# ECGAquisitionBoard.net
KiCad netlist of a schematic drawn in Altium Designer
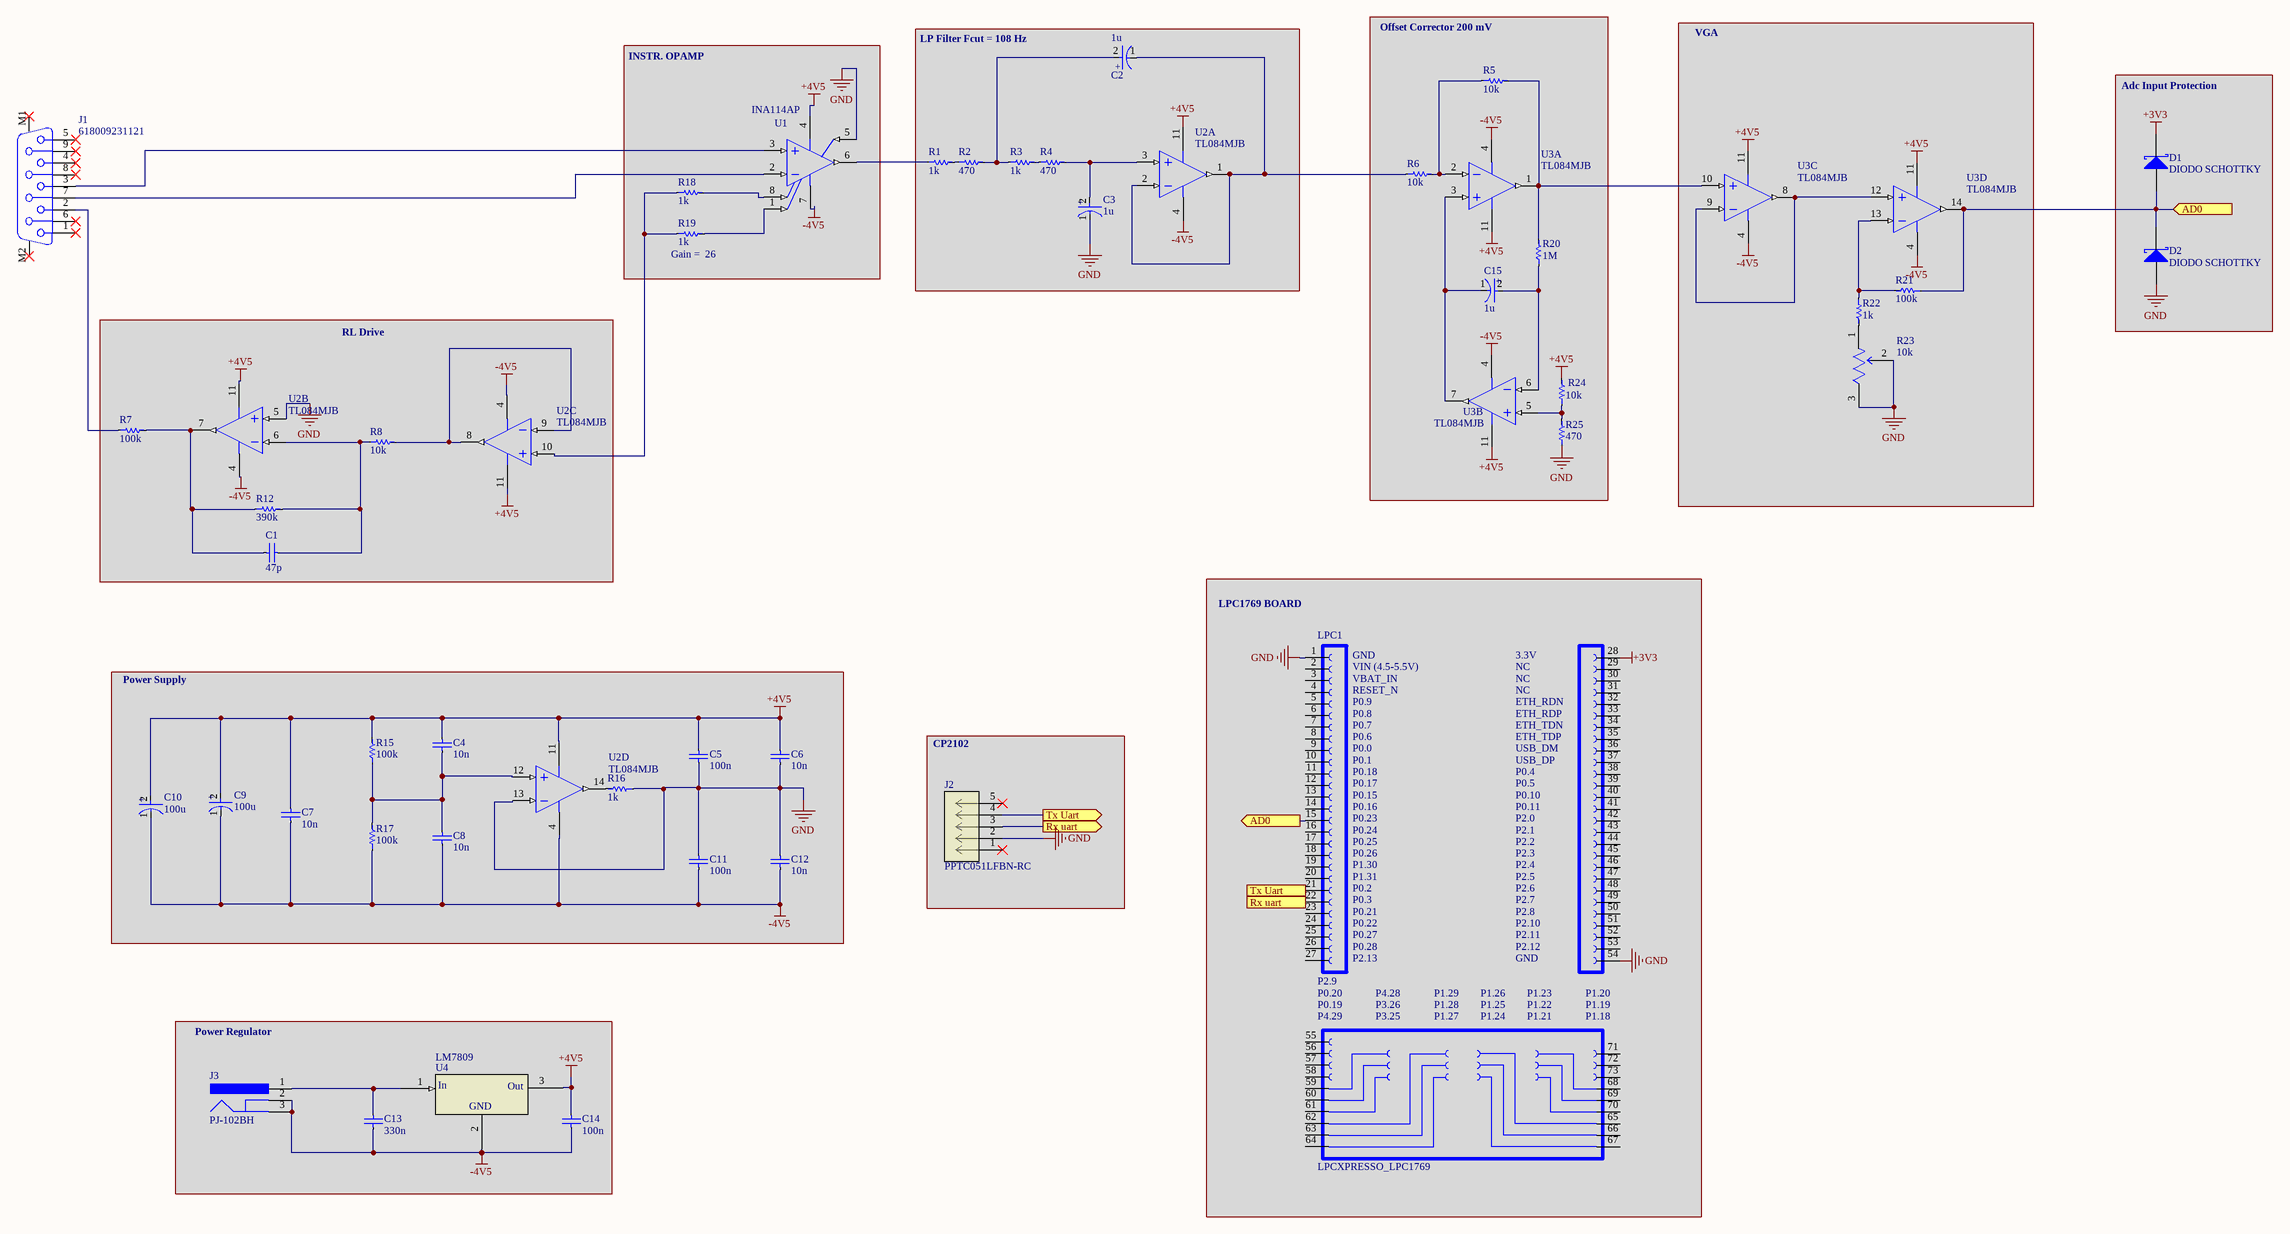
[diagram p0: ECGAquisitionBoard.SchDoc]

(export (version "E")
  (design (tool "Eeschema 10.0.6"))
  (components
    (comp (ref "C1")
      (value "47p")
      (footprint "CAP SMD 1206")
      (description "CAP 330nF 50V ±10% 1206 (3216 Metric) Thickness 1.9mm SMD")
      (fields (field (name "TOLERANCE") "Â±10%"))
      (libsource (lib "ECGAquisitionBoard") (part "CAP SMD 1206"))
    )
    (comp (ref "C2")
      (value "1u")
      (footprint "FP-RAD-TH-D_5_0_5-L_11_1-MFG")
      (description "Aluminum Electrolytic Capacitors (Radial Lead Type) AEC-Q200 Qualified 10uF ±20% 50V")
      (fields (field (name "TOLERANCE") "20%"))
      (libsource (lib "Altium Content Vault") (part "a00bbbee19879c290e62620ae7e47b1"))
    )
    (comp (ref "C3")
      (value "1u")
      (footprint "FP-RAD-TH-D_5_0_5-L_11_1-MFG")
      (description "Aluminum Electrolytic Capacitors (Radial Lead Type) AEC-Q200 Qualified 10uF ±20% 50V")
      (fields (field (name "TOLERANCE") "20%"))
      (libsource (lib "Altium Content Vault") (part "a00bbbee19879c290e62620ae7e47b1"))
    )
    (comp (ref "C4")
      (value "10n")
      (footprint "CAP SMD 1206")
      (description "CAP 330nF 50V ±10% 1206 (3216 Metric) Thickness 1.9mm SMD")
      (fields (field (name "TOLERANCE") "Â±10%"))
      (libsource (lib "ECGAquisitionBoard") (part "CAP SMD 1206"))
    )
    (comp (ref "C5")
      (value "100n")
      (footprint "CAP SMD 1206")
      (description "CAP 330nF 50V ±10% 1206 (3216 Metric) Thickness 1.9mm SMD")
      (fields (field (name "TOLERANCE") "Â±10%"))
      (libsource (lib "ECGAquisitionBoard") (part "CAP SMD 1206"))
    )
    (comp (ref "C6")
      (value "10n")
      (footprint "CAP SMD 1206")
      (description "CAP 330nF 50V ±10% 1206 (3216 Metric) Thickness 1.9mm SMD")
      (fields (field (name "TOLERANCE") "Â±10%"))
      (libsource (lib "ECGAquisitionBoard") (part "CAP SMD 1206"))
    )
    (comp (ref "C7")
      (value "10n")
      (footprint "CAP SMD 1206")
      (description "CAP 330nF 50V ±10% 1206 (3216 Metric) Thickness 1.9mm SMD")
      (fields (field (name "TOLERANCE") "Â±10%"))
      (libsource (lib "ECGAquisitionBoard") (part "CAP SMD 1206"))
    )
    (comp (ref "C8")
      (value "10n")
      (footprint "CAP SMD 1206")
      (description "CAP 330nF 50V ±10% 1206 (3216 Metric) Thickness 1.9mm SMD")
      (fields (field (name "TOLERANCE") "Â±10%"))
      (libsource (lib "ECGAquisitionBoard") (part "CAP SMD 1206"))
    )
    (comp (ref "C9")
      (value "100u")
      (footprint "FP-RAD-TH-D_5_0_5-L_11_1-MFG")
      (description "Aluminum Electrolytic Capacitors (Radial Lead Type) AEC-Q200 Qualified 10uF ±20% 50V")
      (fields (field (name "TOLERANCE") "20%"))
      (libsource (lib "Altium Content Vault") (part "a00bbbee19879c290e62620ae7e47b1"))
    )
    (comp (ref "C10")
      (value "100u")
      (footprint "FP-RAD-TH-D_5_0_5-L_11_1-MFG")
      (description "Aluminum Electrolytic Capacitors (Radial Lead Type) AEC-Q200 Qualified 10uF ±20% 50V")
      (fields (field (name "TOLERANCE") "20%"))
      (libsource (lib "Altium Content Vault") (part "a00bbbee19879c290e62620ae7e47b1"))
    )
    (comp (ref "C11")
      (value "100n")
      (footprint "CAP SMD 1206")
      (description "CAP 330nF 50V ±10% 1206 (3216 Metric) Thickness 1.9mm SMD")
      (fields (field (name "TOLERANCE") "Â±10%"))
      (libsource (lib "ECGAquisitionBoard") (part "CAP SMD 1206"))
    )
    (comp (ref "C12")
      (value "10n")
      (footprint "CAP SMD 1206")
      (description "CAP 330nF 50V ±10% 1206 (3216 Metric) Thickness 1.9mm SMD")
      (fields (field (name "TOLERANCE") "Â±10%"))
      (libsource (lib "ECGAquisitionBoard") (part "CAP SMD 1206"))
    )
    (comp (ref "C13")
      (value "330n")
      (footprint "CAP SMD 1206")
      (description "CAP 330nF 50V ±10% 1206 (3216 Metric) Thickness 1.9mm SMD")
      (fields (field (name "TOLERANCE") "Â±10%"))
      (libsource (lib "ECGAquisitionBoard") (part "CAP SMD 1206"))
    )
    (comp (ref "C14")
      (value "100n")
      (footprint "CAP SMD 1206")
      (description "CAP 330nF 50V ±10% 1206 (3216 Metric) Thickness 1.9mm SMD")
      (fields (field (name "TOLERANCE") "Â±10%"))
      (libsource (lib "ECGAquisitionBoard") (part "CAP SMD 1206"))
    )
    (comp (ref "C15")
      (value "1u")
      (footprint "FP-RAD-TH-D_5_0_5-L_11_1-MFG")
      (description "Aluminum Electrolytic Capacitors (Radial Lead Type) AEC-Q200 Qualified 10uF ±20% 50V")
      (fields (field (name "TOLERANCE") "20%"))
      (libsource (lib "Altium Content Vault") (part "a00bbbee19879c290e62620ae7e47b1"))
    )
    (comp (ref "D1")
      (value "DIODO SCHOTTKY")
      (footprint "DO-41")
      (description "Diodo Schottky")
      (libsource (lib "ECGAquisitionBoard") (part "DIODO SCHOTTKY"))
    )
    (comp (ref "D2")
      (value "DIODO SCHOTTKY")
      (footprint "DO-41")
      (description "Diodo Schottky")
      (libsource (lib "ECGAquisitionBoard") (part "DIODO SCHOTTKY"))
    )
    (comp (ref "J1")
      (value "618009231121")
      (footprint "618009231121")
      (libsource (lib "Altium Content Vault") (part "D-Sub_Female_09p"))
    )
    (comp (ref "J2")
      (value "PPTC051LFBN-RC")
      (footprint "HEADER 5 F 90DEG")
      (description "Description")
      (fields (field (name "COPYRIGHT") "Copyright (C) 2025 Ultra Librarian. All rights reserved."))
      (libsource (lib "ECGAquisitionBoard") (part "HEADER 5 F 90DEG"))
    )
    (comp (ref "J3")
      (value "PJ-102BH")
      (footprint "CUI-PJ-102BH_V")
      (fields (field (name "MANUFACTURER") "CUIInc."))
      (libsource (lib "Altium Content Vault") (part "JACK-2CD3-RN"))
    )
    (comp (ref "LPC1")
      (value "LPCXPRESSO_LPC1769")
      (footprint "LPCXPRESSO_LPC1769")
      (fields (field (name "MF") "Embedded Artists") (field (name "MP") "LPCXPRESSO LPC1769"))
      (libsource (lib "ECGAquisitionBoard") (part "LPCXPRESSO_LPC1769"))
    )
    (comp (ref "R1")
      (value "1k")
      (footprint "RES SMD 1206")
      (description "Resistencia")
      (fields (field (name "PUBLISHER") "Altium Limited"))
      (libsource (lib "ECGAquisitionBoard") (part "RES SMD 1206"))
    )
    (comp (ref "R2")
      (value "470")
      (footprint "RES SMD 1206")
      (description "Resistencia")
      (fields (field (name "PUBLISHER") "Altium Limited"))
      (libsource (lib "ECGAquisitionBoard") (part "RES SMD 1206"))
    )
    (comp (ref "R3")
      (value "1k")
      (footprint "RES SMD 1206")
      (description "Resistencia")
      (fields (field (name "PUBLISHER") "Altium Limited"))
      (libsource (lib "ECGAquisitionBoard") (part "RES SMD 1206"))
    )
    (comp (ref "R4")
      (value "470")
      (footprint "RES SMD 1206")
      (description "Resistencia")
      (fields (field (name "PUBLISHER") "Altium Limited"))
      (libsource (lib "ECGAquisitionBoard") (part "RES SMD 1206"))
    )
    (comp (ref "R5")
      (value "10k")
      (footprint "RES SMD 1206")
      (description "Resistencia")
      (fields (field (name "PUBLISHER") "Altium Limited"))
      (libsource (lib "ECGAquisitionBoard") (part "RES SMD 1206"))
    )
    (comp (ref "R6")
      (value "10k")
      (footprint "RES SMD 1206")
      (description "Resistencia")
      (fields (field (name "PUBLISHER") "Altium Limited"))
      (libsource (lib "ECGAquisitionBoard") (part "RES SMD 1206"))
    )
    (comp (ref "R7")
      (value "100k")
      (footprint "RES SMD 1206")
      (description "Resistencia")
      (fields (field (name "PUBLISHER") "Altium Limited"))
      (libsource (lib "ECGAquisitionBoard") (part "RES SMD 1206"))
    )
    (comp (ref "R8")
      (value "10k")
      (footprint "RES SMD 1206")
      (description "Resistencia")
      (fields (field (name "PUBLISHER") "Altium Limited"))
      (libsource (lib "ECGAquisitionBoard") (part "RES SMD 1206"))
    )
    (comp (ref "R12")
      (value "390k")
      (footprint "RES SMD 1206")
      (description "Resistencia")
      (fields (field (name "PUBLISHER") "Altium Limited"))
      (libsource (lib "ECGAquisitionBoard") (part "RES SMD 1206"))
    )
    (comp (ref "R15")
      (value "100k")
      (footprint "RES SMD 1206")
      (description "Resistencia")
      (fields (field (name "PUBLISHER") "Altium Limited"))
      (libsource (lib "ECGAquisitionBoard") (part "RES SMD 1206"))
    )
    (comp (ref "R16")
      (value "1k")
      (footprint "RES SMD 1206")
      (description "Resistencia")
      (fields (field (name "PUBLISHER") "Altium Limited"))
      (libsource (lib "ECGAquisitionBoard") (part "RES SMD 1206"))
    )
    (comp (ref "R17")
      (value "100k")
      (footprint "RES SMD 1206")
      (description "Resistencia")
      (fields (field (name "PUBLISHER") "Altium Limited"))
      (libsource (lib "ECGAquisitionBoard") (part "RES SMD 1206"))
    )
    (comp (ref "R18")
      (value "1k")
      (footprint "RES SMD 1206")
      (description "Resistencia")
      (fields (field (name "PUBLISHER") "Altium Limited"))
      (libsource (lib "ECGAquisitionBoard") (part "RES SMD 1206"))
    )
    (comp (ref "R19")
      (value "1k")
      (footprint "RES SMD 1206")
      (description "Resistencia")
      (fields (field (name "PUBLISHER") "Altium Limited"))
      (libsource (lib "ECGAquisitionBoard") (part "RES SMD 1206"))
    )
    (comp (ref "R20")
      (value "1M")
      (footprint "RES SMD 1206")
      (description "Resistencia")
      (fields (field (name "PUBLISHER") "Altium Limited"))
      (libsource (lib "ECGAquisitionBoard") (part "RES SMD 1206"))
    )
    (comp (ref "R21")
      (value "100k")
      (footprint "RES SMD 1206")
      (description "Resistencia")
      (fields (field (name "PUBLISHER") "Altium Limited"))
      (libsource (lib "ECGAquisitionBoard") (part "RES SMD 1206"))
    )
    (comp (ref "R22")
      (value "1k")
      (footprint "RES SMD 1206")
      (description "Resistencia")
      (fields (field (name "PUBLISHER") "Altium Limited"))
      (libsource (lib "ECGAquisitionBoard") (part "RES SMD 1206"))
    )
    (comp (ref "R23")
      (value "10k")
      (footprint "FP-3296W-MFG")
      (description "TRIMMER 10K OHM 0.5W PC PIN TOP")
      (fields (field (name "TOLERANCE") "10%"))
      (libsource (lib "Altium Content Vault") (part "194907ebf2981c0cdd5d9631a0af656"))
    )
    (comp (ref "R24")
      (value "10k")
      (footprint "RES SMD 1206")
      (description "Resistencia")
      (fields (field (name "PUBLISHER") "Altium Limited"))
      (libsource (lib "ECGAquisitionBoard") (part "RES SMD 1206"))
    )
    (comp (ref "R25")
      (value "470")
      (footprint "RES SMD 1206")
      (description "Resistencia")
      (fields (field (name "PUBLISHER") "Altium Limited"))
      (libsource (lib "ECGAquisitionBoard") (part "RES SMD 1206"))
    )
    (comp (ref "U1")
      (value "INA114AP")
      (footprint "P0008A")
      (description "Precision Instrumentation Amplifier, -40 to 85 degC, 8-pin DIP (P8), Green (RoHS & no Sb/Br)")
      (fields (field (name "MANUFACTURER") "Texas Instruments"))
      (libsource (lib "Altium Content Vault") (part "TI-INA1XX-8"))
    )
    (comp (ref "U2")
      (value "TL084MJB")
      (footprint "J0014A")
      (description "High Speed JFET-Input Quad Operational Amplifier, -55 to 125 degC, 14-pin DIP (J14)")
      (fields (field (name "MANUFACTURER") "Texas Instruments"))
      (libsource (lib "Altium Content Vault") (part "TI-TLXX4X_MC3403-X14"))
    )
    (comp (ref "U3")
      (value "TL084MJB")
      (footprint "J0014A")
      (description "High Speed JFET-Input Quad Operational Amplifier, -55 to 125 degC, 14-pin DIP (J14)")
      (fields (field (name "MANUFACTURER") "Texas Instruments"))
      (libsource (lib "Altium Content Vault") (part "TI-TLXX4X_MC3403-X14"))
    )
    (comp (ref "U4")
      (value "LM7809")
      (footprint "LM7809")
      (description "No Description Available")
      (fields
        (field (name "MANUFACTURER_PART_NUMBER") "MC7809CTG")
        (field (name "COPYRIGHT") "Copyright (C) 2025 Ultra Librarian. All rights reserved.")
      )
      (libsource (lib "ECGAquisitionBoard") (part "LM7809"))
    )
  )
  (nets
    (net (code "1") (name "+3V3") (class "Default")
      (node (ref "D1") (pin "2") (pinfunction "K_2") (pintype "passive"))
      (node (ref "LPC1") (pin "28") (pinfunction "28_28") (pintype "passive"))
    )
    (net (code "2") (name "+4V5") (class "Default")
      (node (ref "C10") (pin "2") (pinfunction "A_2") (pintype "passive"))
      (node (ref "C14") (pin "2") (pinfunction "2_2") (pintype "passive"))
      (node (ref "C4") (pin "2") (pinfunction "2_2") (pintype "passive"))
      (node (ref "C5") (pin "2") (pinfunction "2_2") (pintype "passive"))
      (node (ref "C6") (pin "2") (pinfunction "2_2") (pintype "passive"))
      (node (ref "C7") (pin "2") (pinfunction "2_2") (pintype "passive"))
      (node (ref "C9") (pin "2") (pinfunction "A_2") (pintype "passive"))
      (node (ref "R15") (pin "2") (pinfunction "2_2") (pintype "passive"))
      (node (ref "R24") (pin "2") (pinfunction "2_2") (pintype "passive"))
      (node (ref "U1") (pin "4") (pinfunction "V-_4") (pintype "power_in"))
      (node (ref "U2") (pin "11") (pinfunction "VCC-_11") (pintype "power_in"))
      (node (ref "U3") (pin "11") (pinfunction "VCC-_11") (pintype "power_in"))
      (node (ref "U4") (pin "3") (pinfunction "OUTPUT_3") (pintype "power_in"))
    )
    (net (code "3") (name "-4V5") (class "Default")
      (node (ref "C10") (pin "1") (pinfunction "C_1") (pintype "passive"))
      (node (ref "C11") (pin "1") (pinfunction "1_1") (pintype "passive"))
      (node (ref "C12") (pin "1") (pinfunction "1_1") (pintype "passive"))
      (node (ref "C13") (pin "1") (pinfunction "1_1") (pintype "passive"))
      (node (ref "C14") (pin "1") (pinfunction "1_1") (pintype "passive"))
      (node (ref "C7") (pin "1") (pinfunction "1_1") (pintype "passive"))
      (node (ref "C8") (pin "1") (pinfunction "1_1") (pintype "passive"))
      (node (ref "C9") (pin "1") (pinfunction "C_1") (pintype "passive"))
      (node (ref "J3") (pin "2") (pinfunction "2_2") (pintype "passive"))
      (node (ref "J3") (pin "3") (pinfunction "3_3") (pintype "passive"))
      (node (ref "R17") (pin "1") (pinfunction "1_1") (pintype "passive"))
      (node (ref "U1") (pin "7") (pinfunction "V+_7") (pintype "power_in"))
      (node (ref "U2") (pin "4") (pinfunction "VCC+_4") (pintype "power_in"))
      (node (ref "U3") (pin "4") (pinfunction "VCC+_4") (pintype "power_in"))
      (node (ref "U4") (pin "2") (pinfunction "GROUND_2") (pintype "power_in"))
    )
    (net (code "4") (name "/AD0") (class "Default")
      (node (ref "D1") (pin "1") (pinfunction "A_1") (pintype "passive"))
      (node (ref "D2") (pin "2") (pinfunction "K_2") (pintype "passive"))
      (node (ref "LPC1") (pin "15") (pinfunction "15_15") (pintype "passive"))
      (node (ref "R21") (pin "1") (pinfunction "1_1") (pintype "passive"))
      (node (ref "U3") (pin "14") (pinfunction "OUT4_14") (pintype "output"))
    )
    (net (code "5") (name "/Rx uart") (class "Default")
      (node (ref "J2") (pin "3") (pinfunction "3_3") (pintype "passive"))
      (node (ref "LPC1") (pin "22") (pinfunction "22_22") (pintype "passive"))
    )
    (net (code "6") (name "/Tx Uart") (class "Default")
      (node (ref "J2") (pin "4") (pinfunction "4_4") (pintype "passive"))
      (node (ref "LPC1") (pin "21") (pinfunction "21_21") (pintype "passive"))
    )
    (net (code "7") (name "GND") (class "Default")
      (node (ref "C11") (pin "2") (pinfunction "2_2") (pintype "passive"))
      (node (ref "C12") (pin "2") (pinfunction "2_2") (pintype "passive"))
      (node (ref "C3") (pin "1") (pinfunction "C_1") (pintype "passive"))
      (node (ref "C5") (pin "1") (pinfunction "1_1") (pintype "passive"))
      (node (ref "C6") (pin "1") (pinfunction "1_1") (pintype "passive"))
      (node (ref "D2") (pin "1") (pinfunction "A_1") (pintype "passive"))
      (node (ref "J2") (pin "2") (pinfunction "2_2") (pintype "passive"))
      (node (ref "LPC1") (pin "1") (pinfunction "1_1") (pintype "passive"))
      (node (ref "LPC1") (pin "54") (pinfunction "54_54") (pintype "passive"))
      (node (ref "R16") (pin "1") (pinfunction "1_1") (pintype "passive"))
      (node (ref "R23") (pin "2") (pinfunction "WIPER_2") (pintype "passive"))
      (node (ref "R23") (pin "3") (pinfunction "CW_3") (pintype "passive"))
      (node (ref "R25") (pin "1") (pinfunction "1_1") (pintype "passive"))
      (node (ref "U1") (pin "5") (pinfunction "REF_5") (pintype "input"))
      (node (ref "U2") (pin "13") (pinfunction "IN4-_13") (pintype "input"))
      (node (ref "U2") (pin "5") (pinfunction "IN2+_5") (pintype "input"))
    )
    (net (code "8") (name "Net-(C2-A)") (class "Default")
      (node (ref "C2") (pin "2") (pinfunction "A_2") (pintype "passive"))
      (node (ref "R2") (pin "2") (pinfunction "2_2") (pintype "passive"))
      (node (ref "R3") (pin "1") (pinfunction "1_1") (pintype "passive"))
    )
    (net (code "9") (name "Net-(C2-C)") (class "Default")
      (node (ref "C2") (pin "1") (pinfunction "C_1") (pintype "passive"))
      (node (ref "R6") (pin "1") (pinfunction "1_1") (pintype "passive"))
      (node (ref "U2") (pin "1") (pinfunction "OUT1_1") (pintype "output"))
      (node (ref "U2") (pin "2") (pinfunction "IN1-_2") (pintype "input"))
    )
    (net (code "10") (name "Net-(C3-A)") (class "Default")
      (node (ref "C3") (pin "2") (pinfunction "A_2") (pintype "passive"))
      (node (ref "R4") (pin "2") (pinfunction "2_2") (pintype "passive"))
      (node (ref "U2") (pin "3") (pinfunction "IN1+_3") (pintype "input"))
    )
    (net (code "11") (name "Net-(C15-A)") (class "Default")
      (node (ref "C15") (pin "2") (pinfunction "A_2") (pintype "passive"))
      (node (ref "R20") (pin "1") (pinfunction "1_1") (pintype "passive"))
      (node (ref "U3") (pin "6") (pinfunction "IN2-_6") (pintype "input"))
    )
    (net (code "12") (name "Net-(C15-C)") (class "Default")
      (node (ref "C15") (pin "1") (pinfunction "C_1") (pintype "passive"))
      (node (ref "U3") (pin "3") (pinfunction "IN1+_3") (pintype "input"))
      (node (ref "U3") (pin "7") (pinfunction "OUT2_7") (pintype "output"))
    )
    (net (code "13") (name "Net-(J1-Pad2)") (class "Default")
      (node (ref "J1") (pin "2") (pinfunction "2_2") (pintype "passive"))
      (node (ref "R7") (pin "1") (pinfunction "1_1") (pintype "passive"))
    )
    (net (code "14") (name "Net-(R1-Pad2)") (class "Default")
      (node (ref "R1") (pin "2") (pinfunction "2_2") (pintype "passive"))
      (node (ref "R2") (pin "1") (pinfunction "1_1") (pintype "passive"))
    )
    (net (code "15") (name "Net-(R3-Pad2)") (class "Default")
      (node (ref "R3") (pin "2") (pinfunction "2_2") (pintype "passive"))
      (node (ref "R4") (pin "1") (pinfunction "1_1") (pintype "passive"))
    )
    (net (code "16") (name "Net-(R18-Pad2)") (class "Default")
      (node (ref "R18") (pin "2") (pinfunction "2_2") (pintype "passive"))
      (node (ref "U1") (pin "8") (pinfunction "RG_8") (pintype "input"))
    )
    (net (code "17") (name "Net-(R19-Pad2)") (class "Default")
      (node (ref "R19") (pin "2") (pinfunction "2_2") (pintype "passive"))
      (node (ref "U1") (pin "1") (pinfunction "RG_1") (pintype "input"))
    )
    (net (code "18") (name "Net-(R23-CCW)") (class "Default")
      (node (ref "R22") (pin "2") (pinfunction "2_2") (pintype "passive"))
      (node (ref "R23") (pin "1") (pinfunction "CCW_1") (pintype "passive"))
    )
    (net (code "19") (name "Net-(U1-VIN+)") (class "Default")
      (node (ref "J1") (pin "3") (pinfunction "3_3") (pintype "passive"))
      (node (ref "U1") (pin "3") (pinfunction "VIN+_3") (pintype "input"))
    )
    (net (code "20") (name "Net-(U1-VIN-)") (class "Default")
      (node (ref "J1") (pin "7") (pinfunction "7_7") (pintype "passive"))
      (node (ref "U1") (pin "2") (pinfunction "VIN-_2") (pintype "input"))
    )
    (net (code "21") (name "Net-(U1-VO)") (class "Default")
      (node (ref "R1") (pin "1") (pinfunction "1_1") (pintype "passive"))
      (node (ref "U1") (pin "6") (pinfunction "VO_6") (pintype "output"))
    )
    (net (code "22") (name "Net-(U2B-IN2-)") (class "Default")
      (node (ref "C1") (pin "2") (pinfunction "2_2") (pintype "passive"))
      (node (ref "R12") (pin "2") (pinfunction "2_2") (pintype "passive"))
      (node (ref "R8") (pin "1") (pinfunction "1_1") (pintype "passive"))
      (node (ref "U2") (pin "6") (pinfunction "IN2-_6") (pintype "input"))
    )
    (net (code "23") (name "Net-(U2B-OUT2)") (class "Default")
      (node (ref "C1") (pin "1") (pinfunction "1_1") (pintype "passive"))
      (node (ref "R12") (pin "1") (pinfunction "1_1") (pintype "passive"))
      (node (ref "R7") (pin "2") (pinfunction "2_2") (pintype "passive"))
      (node (ref "U2") (pin "7") (pinfunction "OUT2_7") (pintype "output"))
    )
    (net (code "24") (name "Net-(U2C-IN3+)") (class "Default")
      (node (ref "R18") (pin "1") (pinfunction "1_1") (pintype "passive"))
      (node (ref "R19") (pin "1") (pinfunction "1_1") (pintype "passive"))
      (node (ref "U2") (pin "10") (pinfunction "IN3+_10") (pintype "input"))
    )
    (net (code "25") (name "Net-(U2C-IN3-)") (class "Default")
      (node (ref "R8") (pin "2") (pinfunction "2_2") (pintype "passive"))
      (node (ref "U2") (pin "8") (pinfunction "OUT3_8") (pintype "output"))
      (node (ref "U2") (pin "9") (pinfunction "IN3-_9") (pintype "input"))
    )
    (net (code "26") (name "Net-(U2D-IN4+)") (class "Default")
      (node (ref "C4") (pin "1") (pinfunction "1_1") (pintype "passive"))
      (node (ref "C8") (pin "2") (pinfunction "2_2") (pintype "passive"))
      (node (ref "R15") (pin "1") (pinfunction "1_1") (pintype "passive"))
      (node (ref "R17") (pin "2") (pinfunction "2_2") (pintype "passive"))
      (node (ref "U2") (pin "12") (pinfunction "IN4+_12") (pintype "input"))
    )
    (net (code "27") (name "Net-(U2D-OUT4)") (class "Default")
      (node (ref "R16") (pin "2") (pinfunction "2_2") (pintype "passive"))
      (node (ref "U2") (pin "14") (pinfunction "OUT4_14") (pintype "output"))
    )
    (net (code "28") (name "Net-(U3A-IN1-)") (class "Default")
      (node (ref "R5") (pin "1") (pinfunction "1_1") (pintype "passive"))
      (node (ref "R6") (pin "2") (pinfunction "2_2") (pintype "passive"))
      (node (ref "U3") (pin "2") (pinfunction "IN1-_2") (pintype "input"))
    )
    (net (code "29") (name "Net-(U3A-OUT1)") (class "Default")
      (node (ref "R20") (pin "2") (pinfunction "2_2") (pintype "passive"))
      (node (ref "R5") (pin "2") (pinfunction "2_2") (pintype "passive"))
      (node (ref "U3") (pin "1") (pinfunction "OUT1_1") (pintype "output"))
      (node (ref "U3") (pin "10") (pinfunction "IN3+_10") (pintype "input"))
    )
    (net (code "30") (name "Net-(U3B-IN2+)") (class "Default")
      (node (ref "R24") (pin "1") (pinfunction "1_1") (pintype "passive"))
      (node (ref "R25") (pin "2") (pinfunction "2_2") (pintype "passive"))
      (node (ref "U3") (pin "5") (pinfunction "IN2+_5") (pintype "input"))
    )
    (net (code "31") (name "Net-(U3C-IN3-)") (class "Default")
      (node (ref "U3") (pin "12") (pinfunction "IN4+_12") (pintype "input"))
      (node (ref "U3") (pin "8") (pinfunction "OUT3_8") (pintype "output"))
      (node (ref "U3") (pin "9") (pinfunction "IN3-_9") (pintype "input"))
    )
    (net (code "32") (name "Net-(U3D-IN4-)") (class "Default")
      (node (ref "R21") (pin "2") (pinfunction "2_2") (pintype "passive"))
      (node (ref "R22") (pin "1") (pinfunction "1_1") (pintype "passive"))
      (node (ref "U3") (pin "13") (pinfunction "IN4-_13") (pintype "input"))
    )
    (net (code "33") (name "Net-(U4-INPUT)") (class "Default")
      (node (ref "C13") (pin "2") (pinfunction "2_2") (pintype "passive"))
      (node (ref "J3") (pin "1") (pinfunction "1_1") (pintype "passive"))
      (node (ref "U4") (pin "1") (pinfunction "INPUT_1") (pintype "input"))
    )
    (net (code "34") (name "unconnected-(J1-Pad1)") (class "Default")
      (node (ref "J1") (pin "1") (pinfunction "1_1") (pintype "passive+no_connect"))
    )
    (net (code "35") (name "unconnected-(J1-Pad4)") (class "Default")
      (node (ref "J1") (pin "4") (pinfunction "4_4") (pintype "passive+no_connect"))
    )
    (net (code "36") (name "unconnected-(J1-Pad5)") (class "Default")
      (node (ref "J1") (pin "5") (pinfunction "5_5") (pintype "passive+no_connect"))
    )
    (net (code "37") (name "unconnected-(J1-Pad6)") (class "Default")
      (node (ref "J1") (pin "6") (pinfunction "6_6") (pintype "passive+no_connect"))
    )
    (net (code "38") (name "unconnected-(J1-Pad8)") (class "Default")
      (node (ref "J1") (pin "8") (pinfunction "8_8") (pintype "passive+no_connect"))
    )
    (net (code "39") (name "unconnected-(J1-Pad9)") (class "Default")
      (node (ref "J1") (pin "9") (pinfunction "9_9") (pintype "passive+no_connect"))
    )
    (net (code "40") (name "unconnected-(J1-PadM1)") (class "Default")
      (node (ref "J1") (pin "M1") (pinfunction "M1_M1") (pintype "passive+no_connect"))
    )
    (net (code "41") (name "unconnected-(J1-PadM2)") (class "Default")
      (node (ref "J1") (pin "M2") (pinfunction "M2_M2") (pintype "passive+no_connect"))
    )
    (net (code "42") (name "unconnected-(J2-Pad1)") (class "Default")
      (node (ref "J2") (pin "1") (pinfunction "1_1") (pintype "passive+no_connect"))
    )
    (net (code "43") (name "unconnected-(J2-Pad5)") (class "Default")
      (node (ref "J2") (pin "5") (pinfunction "5_5") (pintype "passive+no_connect"))
    )
    (net (code "44") (name "unconnected-(LPC1-Pad2)") (class "Default")
      (node (ref "LPC1") (pin "2") (pinfunction "2_2") (pintype "passive"))
    )
    (net (code "45") (name "unconnected-(LPC1-Pad3)") (class "Default")
      (node (ref "LPC1") (pin "3") (pinfunction "3_3") (pintype "passive"))
    )
    (net (code "46") (name "unconnected-(LPC1-Pad4)") (class "Default")
      (node (ref "LPC1") (pin "4") (pinfunction "4_4") (pintype "passive"))
    )
    (net (code "47") (name "unconnected-(LPC1-Pad5)") (class "Default")
      (node (ref "LPC1") (pin "5") (pinfunction "5_5") (pintype "passive"))
    )
    (net (code "48") (name "unconnected-(LPC1-Pad6)") (class "Default")
      (node (ref "LPC1") (pin "6") (pinfunction "6_6") (pintype "passive"))
    )
    (net (code "49") (name "unconnected-(LPC1-Pad7)") (class "Default")
      (node (ref "LPC1") (pin "7") (pinfunction "7_7") (pintype "passive"))
    )
    (net (code "50") (name "unconnected-(LPC1-Pad8)") (class "Default")
      (node (ref "LPC1") (pin "8") (pinfunction "8_8") (pintype "passive"))
    )
    (net (code "51") (name "unconnected-(LPC1-Pad9)") (class "Default")
      (node (ref "LPC1") (pin "9") (pinfunction "9_9") (pintype "passive"))
    )
    (net (code "52") (name "unconnected-(LPC1-Pad10)") (class "Default")
      (node (ref "LPC1") (pin "10") (pinfunction "10_10") (pintype "passive"))
    )
    (net (code "53") (name "unconnected-(LPC1-Pad11)") (class "Default")
      (node (ref "LPC1") (pin "11") (pinfunction "11_11") (pintype "passive"))
    )
    (net (code "54") (name "unconnected-(LPC1-Pad12)") (class "Default")
      (node (ref "LPC1") (pin "12") (pinfunction "12_12") (pintype "passive"))
    )
    (net (code "55") (name "unconnected-(LPC1-Pad13)") (class "Default")
      (node (ref "LPC1") (pin "13") (pinfunction "13_13") (pintype "passive"))
    )
    (net (code "56") (name "unconnected-(LPC1-Pad14)") (class "Default")
      (node (ref "LPC1") (pin "14") (pinfunction "14_14") (pintype "passive"))
    )
    (net (code "57") (name "unconnected-(LPC1-Pad16)") (class "Default")
      (node (ref "LPC1") (pin "16") (pinfunction "16_16") (pintype "passive"))
    )
    (net (code "58") (name "unconnected-(LPC1-Pad17)") (class "Default")
      (node (ref "LPC1") (pin "17") (pinfunction "17_17") (pintype "passive"))
    )
    (net (code "59") (name "unconnected-(LPC1-Pad18)") (class "Default")
      (node (ref "LPC1") (pin "18") (pinfunction "18_18") (pintype "passive"))
    )
    (net (code "60") (name "unconnected-(LPC1-Pad19)") (class "Default")
      (node (ref "LPC1") (pin "19") (pinfunction "19_19") (pintype "passive"))
    )
    (net (code "61") (name "unconnected-(LPC1-Pad20)") (class "Default")
      (node (ref "LPC1") (pin "20") (pinfunction "20_20") (pintype "passive"))
    )
    (net (code "62") (name "unconnected-(LPC1-Pad23)") (class "Default")
      (node (ref "LPC1") (pin "23") (pinfunction "23_23") (pintype "passive"))
    )
    (net (code "63") (name "unconnected-(LPC1-Pad24)") (class "Default")
      (node (ref "LPC1") (pin "24") (pinfunction "24_24") (pintype "passive"))
    )
    (net (code "64") (name "unconnected-(LPC1-Pad25)") (class "Default")
      (node (ref "LPC1") (pin "25") (pinfunction "25_25") (pintype "passive"))
    )
    (net (code "65") (name "unconnected-(LPC1-Pad26)") (class "Default")
      (node (ref "LPC1") (pin "26") (pinfunction "26_26") (pintype "passive"))
    )
    (net (code "66") (name "unconnected-(LPC1-Pad27)") (class "Default")
      (node (ref "LPC1") (pin "27") (pinfunction "27_27") (pintype "passive"))
    )
    (net (code "67") (name "unconnected-(LPC1-Pad29)") (class "Default")
      (node (ref "LPC1") (pin "29") (pinfunction "29_29") (pintype "passive"))
    )
    (net (code "68") (name "unconnected-(LPC1-Pad30)") (class "Default")
      (node (ref "LPC1") (pin "30") (pinfunction "30_30") (pintype "passive"))
    )
    (net (code "69") (name "unconnected-(LPC1-Pad31)") (class "Default")
      (node (ref "LPC1") (pin "31") (pinfunction "31_31") (pintype "passive"))
    )
    (net (code "70") (name "unconnected-(LPC1-Pad32)") (class "Default")
      (node (ref "LPC1") (pin "32") (pinfunction "32_32") (pintype "passive"))
    )
    (net (code "71") (name "unconnected-(LPC1-Pad33)") (class "Default")
      (node (ref "LPC1") (pin "33") (pinfunction "33_33") (pintype "passive"))
    )
    (net (code "72") (name "unconnected-(LPC1-Pad34)") (class "Default")
      (node (ref "LPC1") (pin "34") (pinfunction "34_34") (pintype "passive"))
    )
    (net (code "73") (name "unconnected-(LPC1-Pad35)") (class "Default")
      (node (ref "LPC1") (pin "35") (pinfunction "35_35") (pintype "passive"))
    )
    (net (code "74") (name "unconnected-(LPC1-Pad36)") (class "Default")
      (node (ref "LPC1") (pin "36") (pinfunction "36_36") (pintype "passive"))
    )
    (net (code "75") (name "unconnected-(LPC1-Pad37)") (class "Default")
      (node (ref "LPC1") (pin "37") (pinfunction "37_37") (pintype "passive"))
    )
    (net (code "76") (name "unconnected-(LPC1-Pad38)") (class "Default")
      (node (ref "LPC1") (pin "38") (pinfunction "38_38") (pintype "passive"))
    )
    (net (code "77") (name "unconnected-(LPC1-Pad39)") (class "Default")
      (node (ref "LPC1") (pin "39") (pinfunction "39_39") (pintype "passive"))
    )
    (net (code "78") (name "unconnected-(LPC1-Pad40)") (class "Default")
      (node (ref "LPC1") (pin "40") (pinfunction "40_40") (pintype "passive"))
    )
    (net (code "79") (name "unconnected-(LPC1-Pad41)") (class "Default")
      (node (ref "LPC1") (pin "41") (pinfunction "41_41") (pintype "passive"))
    )
    (net (code "80") (name "unconnected-(LPC1-Pad42)") (class "Default")
      (node (ref "LPC1") (pin "42") (pinfunction "42_42") (pintype "passive"))
    )
    (net (code "81") (name "unconnected-(LPC1-Pad43)") (class "Default")
      (node (ref "LPC1") (pin "43") (pinfunction "43_43") (pintype "passive"))
    )
    (net (code "82") (name "unconnected-(LPC1-Pad44)") (class "Default")
      (node (ref "LPC1") (pin "44") (pinfunction "44_44") (pintype "passive"))
    )
    (net (code "83") (name "unconnected-(LPC1-Pad45)") (class "Default")
      (node (ref "LPC1") (pin "45") (pinfunction "45_45") (pintype "passive"))
    )
    (net (code "84") (name "unconnected-(LPC1-Pad46)") (class "Default")
      (node (ref "LPC1") (pin "46") (pinfunction "46_46") (pintype "passive"))
    )
    (net (code "85") (name "unconnected-(LPC1-Pad47)") (class "Default")
      (node (ref "LPC1") (pin "47") (pinfunction "47_47") (pintype "passive"))
    )
    (net (code "86") (name "unconnected-(LPC1-Pad48)") (class "Default")
      (node (ref "LPC1") (pin "48") (pinfunction "48_48") (pintype "passive"))
    )
    (net (code "87") (name "unconnected-(LPC1-Pad49)") (class "Default")
      (node (ref "LPC1") (pin "49") (pinfunction "49_49") (pintype "passive"))
    )
    (net (code "88") (name "unconnected-(LPC1-Pad50)") (class "Default")
      (node (ref "LPC1") (pin "50") (pinfunction "50_50") (pintype "passive"))
    )
    (net (code "89") (name "unconnected-(LPC1-Pad51)") (class "Default")
      (node (ref "LPC1") (pin "51") (pinfunction "51_51") (pintype "passive"))
    )
    (net (code "90") (name "unconnected-(LPC1-Pad52)") (class "Default")
      (node (ref "LPC1") (pin "52") (pinfunction "52_52") (pintype "passive"))
    )
    (net (code "91") (name "unconnected-(LPC1-Pad53)") (class "Default")
      (node (ref "LPC1") (pin "53") (pinfunction "53_53") (pintype "passive"))
    )
    (net (code "92") (name "unconnected-(LPC1-Pad55)") (class "Default")
      (node (ref "LPC1") (pin "55") (pinfunction "55_55") (pintype "passive"))
    )
    (net (code "93") (name "unconnected-(LPC1-Pad56)") (class "Default")
      (node (ref "LPC1") (pin "56") (pinfunction "56_56") (pintype "passive"))
    )
    (net (code "94") (name "unconnected-(LPC1-Pad57)") (class "Default")
      (node (ref "LPC1") (pin "57") (pinfunction "57_57") (pintype "passive"))
    )
    (net (code "95") (name "unconnected-(LPC1-Pad58)") (class "Default")
      (node (ref "LPC1") (pin "58") (pinfunction "58_58") (pintype "passive"))
    )
    (net (code "96") (name "unconnected-(LPC1-Pad59)") (class "Default")
      (node (ref "LPC1") (pin "59") (pinfunction "59_59") (pintype "passive"))
    )
    (net (code "97") (name "unconnected-(LPC1-Pad60)") (class "Default")
      (node (ref "LPC1") (pin "60") (pinfunction "60_60") (pintype "passive"))
    )
    (net (code "98") (name "unconnected-(LPC1-Pad61)") (class "Default")
      (node (ref "LPC1") (pin "61") (pinfunction "61_61") (pintype "passive"))
    )
    (net (code "99") (name "unconnected-(LPC1-Pad62)") (class "Default")
      (node (ref "LPC1") (pin "62") (pinfunction "62_62") (pintype "passive"))
    )
    (net (code "100") (name "unconnected-(LPC1-Pad63)") (class "Default")
      (node (ref "LPC1") (pin "63") (pinfunction "63_63") (pintype "passive"))
    )
    (net (code "101") (name "unconnected-(LPC1-Pad64)") (class "Default")
      (node (ref "LPC1") (pin "64") (pinfunction "64_64") (pintype "passive"))
    )
    (net (code "102") (name "unconnected-(LPC1-Pad65)") (class "Default")
      (node (ref "LPC1") (pin "65") (pinfunction "65_65") (pintype "passive"))
    )
    (net (code "103") (name "unconnected-(LPC1-Pad66)") (class "Default")
      (node (ref "LPC1") (pin "66") (pinfunction "66_66") (pintype "passive"))
    )
    (net (code "104") (name "unconnected-(LPC1-Pad67)") (class "Default")
      (node (ref "LPC1") (pin "67") (pinfunction "67_67") (pintype "passive"))
    )
    (net (code "105") (name "unconnected-(LPC1-Pad68)") (class "Default")
      (node (ref "LPC1") (pin "68") (pinfunction "68_68") (pintype "passive"))
    )
    (net (code "106") (name "unconnected-(LPC1-Pad69)") (class "Default")
      (node (ref "LPC1") (pin "69") (pinfunction "69_69") (pintype "passive"))
    )
    (net (code "107") (name "unconnected-(LPC1-Pad70)") (class "Default")
      (node (ref "LPC1") (pin "70") (pinfunction "70_70") (pintype "passive"))
    )
    (net (code "108") (name "unconnected-(LPC1-Pad71)") (class "Default")
      (node (ref "LPC1") (pin "71") (pinfunction "71_71") (pintype "passive"))
    )
    (net (code "109") (name "unconnected-(LPC1-Pad72)") (class "Default")
      (node (ref "LPC1") (pin "72") (pinfunction "72_72") (pintype "passive"))
    )
    (net (code "110") (name "unconnected-(LPC1-Pad73)") (class "Default")
      (node (ref "LPC1") (pin "73") (pinfunction "73_73") (pintype "passive"))
    )
  )
)
